# AmplifierInput.net
KiCad netlist of a schematic drawn in Altium Designer
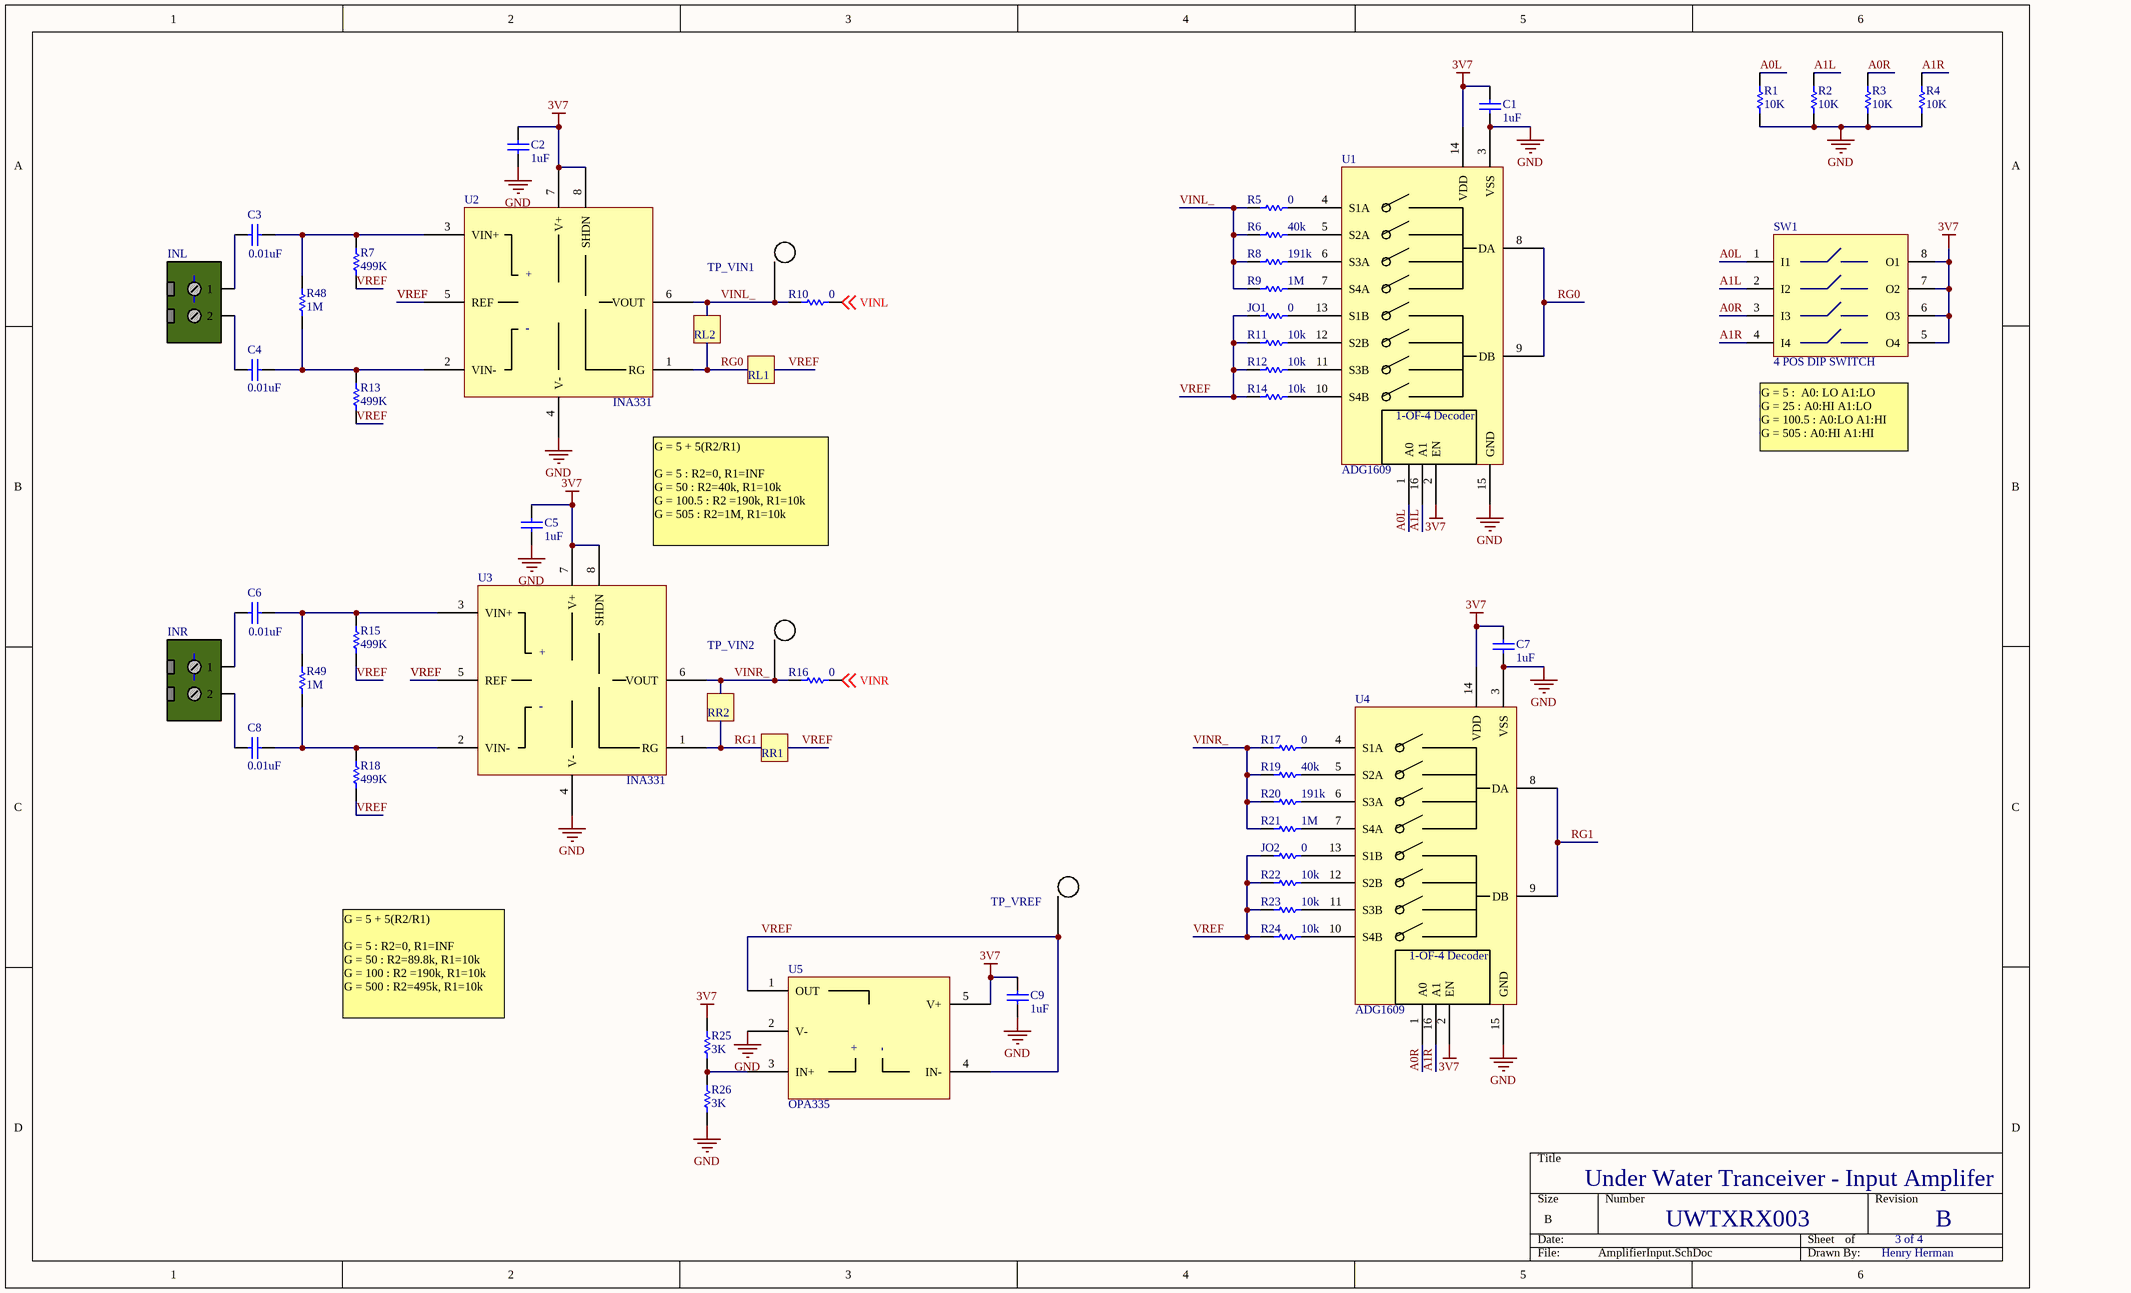
[diagram p0: AmplifierInput.SchDoc]

(export (version "E")
  (design (tool "Eeschema 10.0.6"))
  (components
    (comp (ref "C1")
      (value "1uF")
      (footprint "SM/C_0805")
      (description "CAP")
      (libsource (lib "Henry1_20_2010") (part "CAP"))
    )
    (comp (ref "C2")
      (value "1uF")
      (footprint "SM/C_0805")
      (description "CAP")
      (libsource (lib "Henry1_20_2010") (part "CAP"))
    )
    (comp (ref "C3")
      (value "0.01uF")
      (footprint "SM/C_0805")
      (description "CAP")
      (libsource (lib "Henry1_20_2010") (part "CAP"))
    )
    (comp (ref "C4")
      (value "0.01uF")
      (footprint "SM/C_0805")
      (description "CAP")
      (libsource (lib "Henry1_20_2010") (part "CAP"))
    )
    (comp (ref "C5")
      (value "1uF")
      (footprint "SM/C_0805")
      (description "CAP")
      (libsource (lib "Henry1_20_2010") (part "CAP"))
    )
    (comp (ref "C6")
      (value "0.01uF")
      (footprint "SM/C_0805")
      (description "CAP")
      (libsource (lib "Henry1_20_2010") (part "CAP"))
    )
    (comp (ref "C7")
      (value "1uF")
      (footprint "SM/C_0805")
      (description "CAP")
      (libsource (lib "Henry1_20_2010") (part "CAP"))
    )
    (comp (ref "C8")
      (value "0.01uF")
      (footprint "SM/C_0805")
      (description "CAP")
      (libsource (lib "Henry1_20_2010") (part "CAP"))
    )
    (comp (ref "C9")
      (value "1uF")
      (footprint "SM/C_0805")
      (description "CAP")
      (libsource (lib "Henry1_20_2010") (part "CAP"))
    )
    (comp (ref "INL")
      (value "TERM BLOCK 2POS")
      (footprint "Conn-ScrewTerminal-2pin-Phoenix")
      (libsource (lib "Henry1_20_2010") (part "2Pin-PhoenixTerminalBlock"))
    )
    (comp (ref "INR")
      (value "TERM BLOCK 2POS")
      (footprint "Conn-ScrewTerminal-2pin-Phoenix")
      (libsource (lib "Henry1_20_2010") (part "2Pin-PhoenixTerminalBlock"))
    )
    (comp (ref "JO1")
      (value "0")
      (footprint "SM/R_0805")
      (description "Resistor")
      (fields (field (name "Comment") "Res") (field (name "PUBLISHER") "Altium Limited"))
      (libsource (lib "Henry1_20_2010") (part "Res"))
    )
    (comp (ref "JO2")
      (value "0")
      (footprint "SM/R_0805")
      (description "Resistor")
      (fields (field (name "Comment") "Res") (field (name "PUBLISHER") "Altium Limited"))
      (libsource (lib "Henry1_20_2010") (part "Res"))
    )
    (comp (ref "R1")
      (value "10K")
      (footprint "SM/R_0805")
      (description "Resistor")
      (fields (field (name "Comment") "Res") (field (name "PUBLISHER") "Altium Limited"))
      (libsource (lib "Henry1_20_2010") (part "Res"))
    )
    (comp (ref "R2")
      (value "10K")
      (footprint "SM/R_0805")
      (description "Resistor")
      (fields (field (name "Comment") "Res") (field (name "PUBLISHER") "Altium Limited"))
      (libsource (lib "Henry1_20_2010") (part "Res"))
    )
    (comp (ref "R3")
      (value "10K")
      (footprint "SM/R_0805")
      (description "Resistor")
      (fields (field (name "Comment") "Res") (field (name "PUBLISHER") "Altium Limited"))
      (libsource (lib "Henry1_20_2010") (part "Res"))
    )
    (comp (ref "R4")
      (value "10K")
      (footprint "SM/R_0805")
      (description "Resistor")
      (fields (field (name "Comment") "Res") (field (name "PUBLISHER") "Altium Limited"))
      (libsource (lib "Henry1_20_2010") (part "Res"))
    )
    (comp (ref "R5")
      (value "0")
      (footprint "SM/R_0805")
      (description "Resistor")
      (fields (field (name "Comment") "Res") (field (name "PUBLISHER") "Altium Limited"))
      (libsource (lib "Henry1_20_2010") (part "Res"))
    )
    (comp (ref "R6")
      (value "40k")
      (footprint "SM/R_0805")
      (description "Resistor")
      (fields (field (name "Comment") "Res") (field (name "PUBLISHER") "Altium Limited"))
      (libsource (lib "Henry1_20_2010") (part "Res"))
    )
    (comp (ref "R7")
      (value "499K")
      (footprint "SM/R_0805")
      (description "Resistor")
      (fields (field (name "Comment") "Res") (field (name "PUBLISHER") "Altium Limited"))
      (libsource (lib "Henry1_20_2010") (part "Res"))
    )
    (comp (ref "R8")
      (value "191k")
      (footprint "SM/R_0805")
      (description "Resistor")
      (fields (field (name "Comment") "Res") (field (name "PUBLISHER") "Altium Limited"))
      (libsource (lib "Henry1_20_2010") (part "Res"))
    )
    (comp (ref "R9")
      (value "1M")
      (footprint "SM/R_0805")
      (description "Resistor")
      (fields (field (name "Comment") "Res") (field (name "PUBLISHER") "Altium Limited"))
      (libsource (lib "Henry1_20_2010") (part "Res"))
    )
    (comp (ref "R10")
      (value "0")
      (footprint "SM/R_0805")
      (description "Resistor")
      (fields (field (name "Comment") "Res") (field (name "PUBLISHER") "Altium Limited"))
      (libsource (lib "Henry1_20_2010") (part "Res"))
    )
    (comp (ref "R11")
      (value "10k")
      (footprint "SM/R_0805")
      (description "Resistor")
      (fields (field (name "Comment") "Res") (field (name "PUBLISHER") "Altium Limited"))
      (libsource (lib "Henry1_20_2010") (part "Res"))
    )
    (comp (ref "R12")
      (value "10k")
      (footprint "SM/R_0805")
      (description "Resistor")
      (fields (field (name "Comment") "Res") (field (name "PUBLISHER") "Altium Limited"))
      (libsource (lib "Henry1_20_2010") (part "Res"))
    )
    (comp (ref "R13")
      (value "499K")
      (footprint "SM/R_0805")
      (description "Resistor")
      (fields (field (name "Comment") "Res") (field (name "PUBLISHER") "Altium Limited"))
      (libsource (lib "Henry1_20_2010") (part "Res"))
    )
    (comp (ref "R14")
      (value "10k")
      (footprint "SM/R_0805")
      (description "Resistor")
      (fields (field (name "Comment") "Res") (field (name "PUBLISHER") "Altium Limited"))
      (libsource (lib "Henry1_20_2010") (part "Res"))
    )
    (comp (ref "R15")
      (value "499K")
      (footprint "SM/R_0805")
      (description "Resistor")
      (fields (field (name "Comment") "Res") (field (name "PUBLISHER") "Altium Limited"))
      (libsource (lib "Henry1_20_2010") (part "Res"))
    )
    (comp (ref "R16")
      (value "0")
      (footprint "SM/R_0805")
      (description "Resistor")
      (fields (field (name "Comment") "Res") (field (name "PUBLISHER") "Altium Limited"))
      (libsource (lib "Henry1_20_2010") (part "Res"))
    )
    (comp (ref "R17")
      (value "0")
      (footprint "SM/R_0805")
      (description "Resistor")
      (fields (field (name "Comment") "Res") (field (name "PUBLISHER") "Altium Limited"))
      (libsource (lib "Henry1_20_2010") (part "Res"))
    )
    (comp (ref "R18")
      (value "499K")
      (footprint "SM/R_0805")
      (description "Resistor")
      (fields (field (name "Comment") "Res") (field (name "PUBLISHER") "Altium Limited"))
      (libsource (lib "Henry1_20_2010") (part "Res"))
    )
    (comp (ref "R19")
      (value "40k")
      (footprint "SM/R_0805")
      (description "Resistor")
      (fields (field (name "Comment") "Res") (field (name "PUBLISHER") "Altium Limited"))
      (libsource (lib "Henry1_20_2010") (part "Res"))
    )
    (comp (ref "R20")
      (value "191k")
      (footprint "SM/R_0805")
      (description "Resistor")
      (fields (field (name "Comment") "Res") (field (name "PUBLISHER") "Altium Limited"))
      (libsource (lib "Henry1_20_2010") (part "Res"))
    )
    (comp (ref "R21")
      (value "1M")
      (footprint "SM/R_0805")
      (description "Resistor")
      (fields (field (name "Comment") "Res") (field (name "PUBLISHER") "Altium Limited"))
      (libsource (lib "Henry1_20_2010") (part "Res"))
    )
    (comp (ref "R22")
      (value "10k")
      (footprint "SM/R_0805")
      (description "Resistor")
      (fields (field (name "Comment") "Res") (field (name "PUBLISHER") "Altium Limited"))
      (libsource (lib "Henry1_20_2010") (part "Res"))
    )
    (comp (ref "R23")
      (value "10k")
      (footprint "SM/R_0805")
      (description "Resistor")
      (fields (field (name "Comment") "Res") (field (name "PUBLISHER") "Altium Limited"))
      (libsource (lib "Henry1_20_2010") (part "Res"))
    )
    (comp (ref "R24")
      (value "10k")
      (footprint "SM/R_0805")
      (description "Resistor")
      (fields (field (name "Comment") "Res") (field (name "PUBLISHER") "Altium Limited"))
      (libsource (lib "Henry1_20_2010") (part "Res"))
    )
    (comp (ref "R25")
      (value "3K")
      (footprint "SM/R_0805")
      (description "Resistor")
      (fields (field (name "Comment") "Res") (field (name "PUBLISHER") "Altium Limited"))
      (libsource (lib "Henry1_20_2010") (part "Res"))
    )
    (comp (ref "R26")
      (value "3K")
      (footprint "SM/R_0805")
      (description "Resistor")
      (fields (field (name "Comment") "Res") (field (name "PUBLISHER") "Altium Limited"))
      (libsource (lib "Henry1_20_2010") (part "Res"))
    )
    (comp (ref "R48")
      (value "1M")
      (footprint "SM/R_0805")
      (description "Resistor")
      (fields (field (name "Comment") "Res") (field (name "PUBLISHER") "Altium Limited"))
      (libsource (lib "Henry1_20_2010") (part "Res"))
    )
    (comp (ref "R49")
      (value "1M")
      (footprint "SM/R_0805")
      (description "Resistor")
      (fields (field (name "Comment") "Res") (field (name "PUBLISHER") "Altium Limited"))
      (libsource (lib "Henry1_20_2010") (part "Res"))
    )
    (comp (ref "SW1")
      (value "4 POS DIP SWITCH")
      (footprint "DIPSW4PIN")
      (libsource (lib "Henry1_20_2010") (part "4 POS DIP SWITCH"))
    )
    (comp (ref "TP_VIN1")
      (value "TEST_PT")
      (footprint "TEST_PT_SMD")
      (libsource (lib "Henry1_20_2010") (part "TEST_PT"))
    )
    (comp (ref "TP_VIN2")
      (value "TEST_PT")
      (footprint "TEST_PT_SMD")
      (libsource (lib "Henry1_20_2010") (part "TEST_PT"))
    )
    (comp (ref "TP_VREF")
      (value "TEST_PT")
      (footprint "TEST_PT_SMD")
      (libsource (lib "Henry1_20_2010") (part "TEST_PT"))
    )
    (comp (ref "U1")
      (value "ADG1609")
      (footprint "TSSOP 16LEAD - Analog Devices - ADG1609")
      (libsource (lib "Henry1_20_2010") (part "ADG1609"))
    )
    (comp (ref "U2")
      (value "INA331")
      (footprint "MSOP-8PIN-TI")
      (libsource (lib "Henry1_20_2010") (part "INA331"))
    )
    (comp (ref "U3")
      (value "INA331")
      (footprint "MSOP-8PIN-TI")
      (libsource (lib "Henry1_20_2010") (part "INA331"))
    )
    (comp (ref "U4")
      (value "ADG1609")
      (footprint "TSSOP 16LEAD - Analog Devices - ADG1609")
      (libsource (lib "Henry1_20_2010") (part "ADG1609"))
    )
    (comp (ref "U5")
      (value "OPA335")
      (footprint "SOT23-5 -TI")
      (libsource (lib "Henry1_20_2010") (part "OPA335"))
    )
  )
  (nets
    (net (code "1") (name "/A0L") (class "Default")
      (node (ref "R1") (pin "2") (pinfunction "2_2") (pintype "passive"))
      (node (ref "SW1") (pin "1") (pinfunction "I1_1") (pintype "passive"))
      (node (ref "U1") (pin "1") (pinfunction "A0_1") (pintype "passive"))
    )
    (net (code "2") (name "/A0R") (class "Default")
      (node (ref "R3") (pin "2") (pinfunction "2_2") (pintype "passive"))
      (node (ref "SW1") (pin "3") (pinfunction "I3_3") (pintype "passive"))
      (node (ref "U4") (pin "1") (pinfunction "A0_1") (pintype "passive"))
    )
    (net (code "3") (name "/A1L") (class "Default")
      (node (ref "R2") (pin "2") (pinfunction "2_2") (pintype "passive"))
      (node (ref "SW1") (pin "2") (pinfunction "I2_2") (pintype "passive"))
      (node (ref "U1") (pin "16") (pinfunction "A1_16") (pintype "passive"))
    )
    (net (code "4") (name "/A1R") (class "Default")
      (node (ref "R4") (pin "2") (pinfunction "2_2") (pintype "passive"))
      (node (ref "SW1") (pin "4") (pinfunction "I4_4") (pintype "passive"))
      (node (ref "U4") (pin "16") (pinfunction "A1_16") (pintype "passive"))
    )
    (net (code "5") (name "/RG0") (class "Default")
      (node (ref "U1") (pin "8") (pinfunction "DA_8") (pintype "passive"))
      (node (ref "U1") (pin "9") (pinfunction "DB_9") (pintype "passive"))
      (node (ref "U2") (pin "1") (pinfunction "RG_1") (pintype "passive"))
    )
    (net (code "6") (name "/RG1") (class "Default")
      (node (ref "U3") (pin "1") (pinfunction "RG_1") (pintype "passive"))
      (node (ref "U4") (pin "8") (pinfunction "DA_8") (pintype "passive"))
      (node (ref "U4") (pin "9") (pinfunction "DB_9") (pintype "passive"))
    )
    (net (code "7") (name "/VINL_") (class "Default")
      (node (ref "R10") (pin "2") (pinfunction "2_2") (pintype "passive"))
      (node (ref "R5") (pin "2") (pinfunction "2_2") (pintype "passive"))
      (node (ref "R6") (pin "2") (pinfunction "2_2") (pintype "passive"))
      (node (ref "R8") (pin "2") (pinfunction "2_2") (pintype "passive"))
      (node (ref "R9") (pin "2") (pinfunction "2_2") (pintype "passive"))
      (node (ref "TP_VIN1") (pin "1") (pinfunction "TP?_1") (pintype "passive"))
      (node (ref "U2") (pin "6") (pinfunction "VOUT_6") (pintype "passive"))
    )
    (net (code "8") (name "/VINR_") (class "Default")
      (node (ref "R16") (pin "2") (pinfunction "2_2") (pintype "passive"))
      (node (ref "R17") (pin "2") (pinfunction "2_2") (pintype "passive"))
      (node (ref "R19") (pin "2") (pinfunction "2_2") (pintype "passive"))
      (node (ref "R20") (pin "2") (pinfunction "2_2") (pintype "passive"))
      (node (ref "R21") (pin "2") (pinfunction "2_2") (pintype "passive"))
      (node (ref "TP_VIN2") (pin "1") (pinfunction "TP?_1") (pintype "passive"))
      (node (ref "U3") (pin "6") (pinfunction "VOUT_6") (pintype "passive"))
    )
    (net (code "9") (name "/VREF") (class "Default")
      (node (ref "JO1") (pin "2") (pinfunction "2_2") (pintype "passive"))
      (node (ref "JO2") (pin "2") (pinfunction "2_2") (pintype "passive"))
      (node (ref "R11") (pin "2") (pinfunction "2_2") (pintype "passive"))
      (node (ref "R12") (pin "2") (pinfunction "2_2") (pintype "passive"))
      (node (ref "R13") (pin "2") (pinfunction "2_2") (pintype "passive"))
      (node (ref "R14") (pin "2") (pinfunction "2_2") (pintype "passive"))
      (node (ref "R15") (pin "2") (pinfunction "2_2") (pintype "passive"))
      (node (ref "R18") (pin "2") (pinfunction "2_2") (pintype "passive"))
      (node (ref "R22") (pin "2") (pinfunction "2_2") (pintype "passive"))
      (node (ref "R23") (pin "2") (pinfunction "2_2") (pintype "passive"))
      (node (ref "R24") (pin "2") (pinfunction "2_2") (pintype "passive"))
      (node (ref "R7") (pin "2") (pinfunction "2_2") (pintype "passive"))
      (node (ref "TP_VREF") (pin "1") (pinfunction "TP?_1") (pintype "passive"))
      (node (ref "U2") (pin "5") (pinfunction "REF_5") (pintype "passive"))
      (node (ref "U3") (pin "5") (pinfunction "REF_5") (pintype "passive"))
      (node (ref "U5") (pin "1") (pinfunction "OUT_1") (pintype "passive"))
      (node (ref "U5") (pin "4") (pinfunction "IN-_4") (pintype "passive"))
    )
    (net (code "10") (name "3V7") (class "Default")
      (node (ref "C1") (pin "1") (pinfunction "1_1") (pintype "passive"))
      (node (ref "C2") (pin "1") (pinfunction "1_1") (pintype "passive"))
      (node (ref "C5") (pin "1") (pinfunction "1_1") (pintype "passive"))
      (node (ref "C7") (pin "1") (pinfunction "1_1") (pintype "passive"))
      (node (ref "C9") (pin "1") (pinfunction "1_1") (pintype "passive"))
      (node (ref "R25") (pin "1") (pinfunction "1_1") (pintype "passive"))
      (node (ref "SW1") (pin "5") (pinfunction "O4_5") (pintype "passive"))
      (node (ref "SW1") (pin "6") (pinfunction "O3_6") (pintype "passive"))
      (node (ref "SW1") (pin "7") (pinfunction "O2_7") (pintype "passive"))
      (node (ref "SW1") (pin "8") (pinfunction "O1_8") (pintype "passive"))
      (node (ref "U1") (pin "14") (pinfunction "VDD_14") (pintype "passive"))
      (node (ref "U1") (pin "2") (pinfunction "EN_2") (pintype "passive"))
      (node (ref "U2") (pin "7") (pinfunction "V+_7") (pintype "passive"))
      (node (ref "U2") (pin "8") (pinfunction "SHDN_8") (pintype "passive"))
      (node (ref "U3") (pin "7") (pinfunction "V+_7") (pintype "passive"))
      (node (ref "U3") (pin "8") (pinfunction "SHDN_8") (pintype "passive"))
      (node (ref "U4") (pin "14") (pinfunction "VDD_14") (pintype "passive"))
      (node (ref "U4") (pin "2") (pinfunction "EN_2") (pintype "passive"))
      (node (ref "U5") (pin "5") (pinfunction "V+_5") (pintype "passive"))
    )
    (net (code "11") (name "GND") (class "Default")
      (node (ref "C1") (pin "2") (pinfunction "2_2") (pintype "passive"))
      (node (ref "C2") (pin "2") (pinfunction "2_2") (pintype "passive"))
      (node (ref "C5") (pin "2") (pinfunction "2_2") (pintype "passive"))
      (node (ref "C7") (pin "2") (pinfunction "2_2") (pintype "passive"))
      (node (ref "C9") (pin "2") (pinfunction "2_2") (pintype "passive"))
      (node (ref "R1") (pin "1") (pinfunction "1_1") (pintype "passive"))
      (node (ref "R2") (pin "1") (pinfunction "1_1") (pintype "passive"))
      (node (ref "R26") (pin "2") (pinfunction "2_2") (pintype "passive"))
      (node (ref "R3") (pin "1") (pinfunction "1_1") (pintype "passive"))
      (node (ref "R4") (pin "1") (pinfunction "1_1") (pintype "passive"))
      (node (ref "U1") (pin "15") (pinfunction "GND_15") (pintype "passive"))
      (node (ref "U1") (pin "3") (pinfunction "VSS_3") (pintype "passive"))
      (node (ref "U2") (pin "4") (pinfunction "V-_4") (pintype "passive"))
      (node (ref "U3") (pin "4") (pinfunction "V-_4") (pintype "passive"))
      (node (ref "U4") (pin "15") (pinfunction "GND_15") (pintype "passive"))
      (node (ref "U4") (pin "3") (pinfunction "VSS_3") (pintype "passive"))
      (node (ref "U5") (pin "2") (pinfunction "V-_2") (pintype "passive"))
    )
    (net (code "12") (name "Net-(C3-Pad2)") (class "Default")
      (node (ref "C3") (pin "2") (pinfunction "2_2") (pintype "passive"))
      (node (ref "INL") (pin "1") (pinfunction "1_1") (pintype "passive"))
    )
    (net (code "13") (name "Net-(C4-Pad2)") (class "Default")
      (node (ref "C4") (pin "2") (pinfunction "2_2") (pintype "passive"))
      (node (ref "INL") (pin "2") (pinfunction "2_2") (pintype "passive"))
    )
    (net (code "14") (name "Net-(C6-Pad2)") (class "Default")
      (node (ref "C6") (pin "2") (pinfunction "2_2") (pintype "passive"))
      (node (ref "INR") (pin "1") (pinfunction "1_1") (pintype "passive"))
    )
    (net (code "15") (name "Net-(C8-Pad2)") (class "Default")
      (node (ref "C8") (pin "2") (pinfunction "2_2") (pintype "passive"))
      (node (ref "INR") (pin "2") (pinfunction "2_2") (pintype "passive"))
    )
    (net (code "16") (name "Net-(U1-S1A)") (class "Default")
      (node (ref "R5") (pin "1") (pinfunction "1_1") (pintype "passive"))
      (node (ref "U1") (pin "4") (pinfunction "S1A_4") (pintype "passive"))
    )
    (net (code "17") (name "Net-(U1-S1B)") (class "Default")
      (node (ref "JO1") (pin "1") (pinfunction "1_1") (pintype "passive"))
      (node (ref "U1") (pin "13") (pinfunction "S1B_13") (pintype "passive"))
    )
    (net (code "18") (name "Net-(U1-S2A)") (class "Default")
      (node (ref "R6") (pin "1") (pinfunction "1_1") (pintype "passive"))
      (node (ref "U1") (pin "5") (pinfunction "S2A_5") (pintype "passive"))
    )
    (net (code "19") (name "Net-(U1-S2B)") (class "Default")
      (node (ref "R11") (pin "1") (pinfunction "1_1") (pintype "passive"))
      (node (ref "U1") (pin "12") (pinfunction "S2B_12") (pintype "passive"))
    )
    (net (code "20") (name "Net-(U1-S3A)") (class "Default")
      (node (ref "R8") (pin "1") (pinfunction "1_1") (pintype "passive"))
      (node (ref "U1") (pin "6") (pinfunction "S3A_6") (pintype "passive"))
    )
    (net (code "21") (name "Net-(U1-S3B)") (class "Default")
      (node (ref "R12") (pin "1") (pinfunction "1_1") (pintype "passive"))
      (node (ref "U1") (pin "11") (pinfunction "S3B_11") (pintype "passive"))
    )
    (net (code "22") (name "Net-(U1-S4A)") (class "Default")
      (node (ref "R9") (pin "1") (pinfunction "1_1") (pintype "passive"))
      (node (ref "U1") (pin "7") (pinfunction "S4A_7") (pintype "passive"))
    )
    (net (code "23") (name "Net-(U1-S4B)") (class "Default")
      (node (ref "R14") (pin "1") (pinfunction "1_1") (pintype "passive"))
      (node (ref "U1") (pin "10") (pinfunction "S4B_10") (pintype "passive"))
    )
    (net (code "24") (name "Net-(U2-VIN+)") (class "Default")
      (node (ref "C3") (pin "1") (pinfunction "1_1") (pintype "passive"))
      (node (ref "R48") (pin "1") (pinfunction "1_1") (pintype "passive"))
      (node (ref "R7") (pin "1") (pinfunction "1_1") (pintype "passive"))
      (node (ref "U2") (pin "3") (pinfunction "VIN+_3") (pintype "passive"))
    )
    (net (code "25") (name "Net-(U2-VIN-)") (class "Default")
      (node (ref "C4") (pin "1") (pinfunction "1_1") (pintype "passive"))
      (node (ref "R13") (pin "1") (pinfunction "1_1") (pintype "passive"))
      (node (ref "R48") (pin "2") (pinfunction "2_2") (pintype "passive"))
      (node (ref "U2") (pin "2") (pinfunction "VIN-_2") (pintype "passive"))
    )
    (net (code "26") (name "Net-(U3-VIN+)") (class "Default")
      (node (ref "C6") (pin "1") (pinfunction "1_1") (pintype "passive"))
      (node (ref "R15") (pin "1") (pinfunction "1_1") (pintype "passive"))
      (node (ref "R49") (pin "1") (pinfunction "1_1") (pintype "passive"))
      (node (ref "U3") (pin "3") (pinfunction "VIN+_3") (pintype "passive"))
    )
    (net (code "27") (name "Net-(U3-VIN-)") (class "Default")
      (node (ref "C8") (pin "1") (pinfunction "1_1") (pintype "passive"))
      (node (ref "R18") (pin "1") (pinfunction "1_1") (pintype "passive"))
      (node (ref "R49") (pin "2") (pinfunction "2_2") (pintype "passive"))
      (node (ref "U3") (pin "2") (pinfunction "VIN-_2") (pintype "passive"))
    )
    (net (code "28") (name "Net-(U4-S1A)") (class "Default")
      (node (ref "R17") (pin "1") (pinfunction "1_1") (pintype "passive"))
      (node (ref "U4") (pin "4") (pinfunction "S1A_4") (pintype "passive"))
    )
    (net (code "29") (name "Net-(U4-S1B)") (class "Default")
      (node (ref "JO2") (pin "1") (pinfunction "1_1") (pintype "passive"))
      (node (ref "U4") (pin "13") (pinfunction "S1B_13") (pintype "passive"))
    )
    (net (code "30") (name "Net-(U4-S2A)") (class "Default")
      (node (ref "R19") (pin "1") (pinfunction "1_1") (pintype "passive"))
      (node (ref "U4") (pin "5") (pinfunction "S2A_5") (pintype "passive"))
    )
    (net (code "31") (name "Net-(U4-S2B)") (class "Default")
      (node (ref "R22") (pin "1") (pinfunction "1_1") (pintype "passive"))
      (node (ref "U4") (pin "12") (pinfunction "S2B_12") (pintype "passive"))
    )
    (net (code "32") (name "Net-(U4-S3A)") (class "Default")
      (node (ref "R20") (pin "1") (pinfunction "1_1") (pintype "passive"))
      (node (ref "U4") (pin "6") (pinfunction "S3A_6") (pintype "passive"))
    )
    (net (code "33") (name "Net-(U4-S3B)") (class "Default")
      (node (ref "R23") (pin "1") (pinfunction "1_1") (pintype "passive"))
      (node (ref "U4") (pin "11") (pinfunction "S3B_11") (pintype "passive"))
    )
    (net (code "34") (name "Net-(U4-S4A)") (class "Default")
      (node (ref "R21") (pin "1") (pinfunction "1_1") (pintype "passive"))
      (node (ref "U4") (pin "7") (pinfunction "S4A_7") (pintype "passive"))
    )
    (net (code "35") (name "Net-(U4-S4B)") (class "Default")
      (node (ref "R24") (pin "1") (pinfunction "1_1") (pintype "passive"))
      (node (ref "U4") (pin "10") (pinfunction "S4B_10") (pintype "passive"))
    )
    (net (code "36") (name "Net-(U5-IN+)") (class "Default")
      (node (ref "R25") (pin "2") (pinfunction "2_2") (pintype "passive"))
      (node (ref "R26") (pin "1") (pinfunction "1_1") (pintype "passive"))
      (node (ref "U5") (pin "3") (pinfunction "IN+_3") (pintype "passive"))
    )
    (net (code "37") (name "VINL") (class "Default")
      (node (ref "R10") (pin "1") (pinfunction "1_1") (pintype "passive"))
    )
    (net (code "38") (name "VINR") (class "Default")
      (node (ref "R16") (pin "1") (pinfunction "1_1") (pintype "passive"))
    )
  )
)
